# Power_Management.net
KiCad netlist of a schematic drawn in Altium Designer
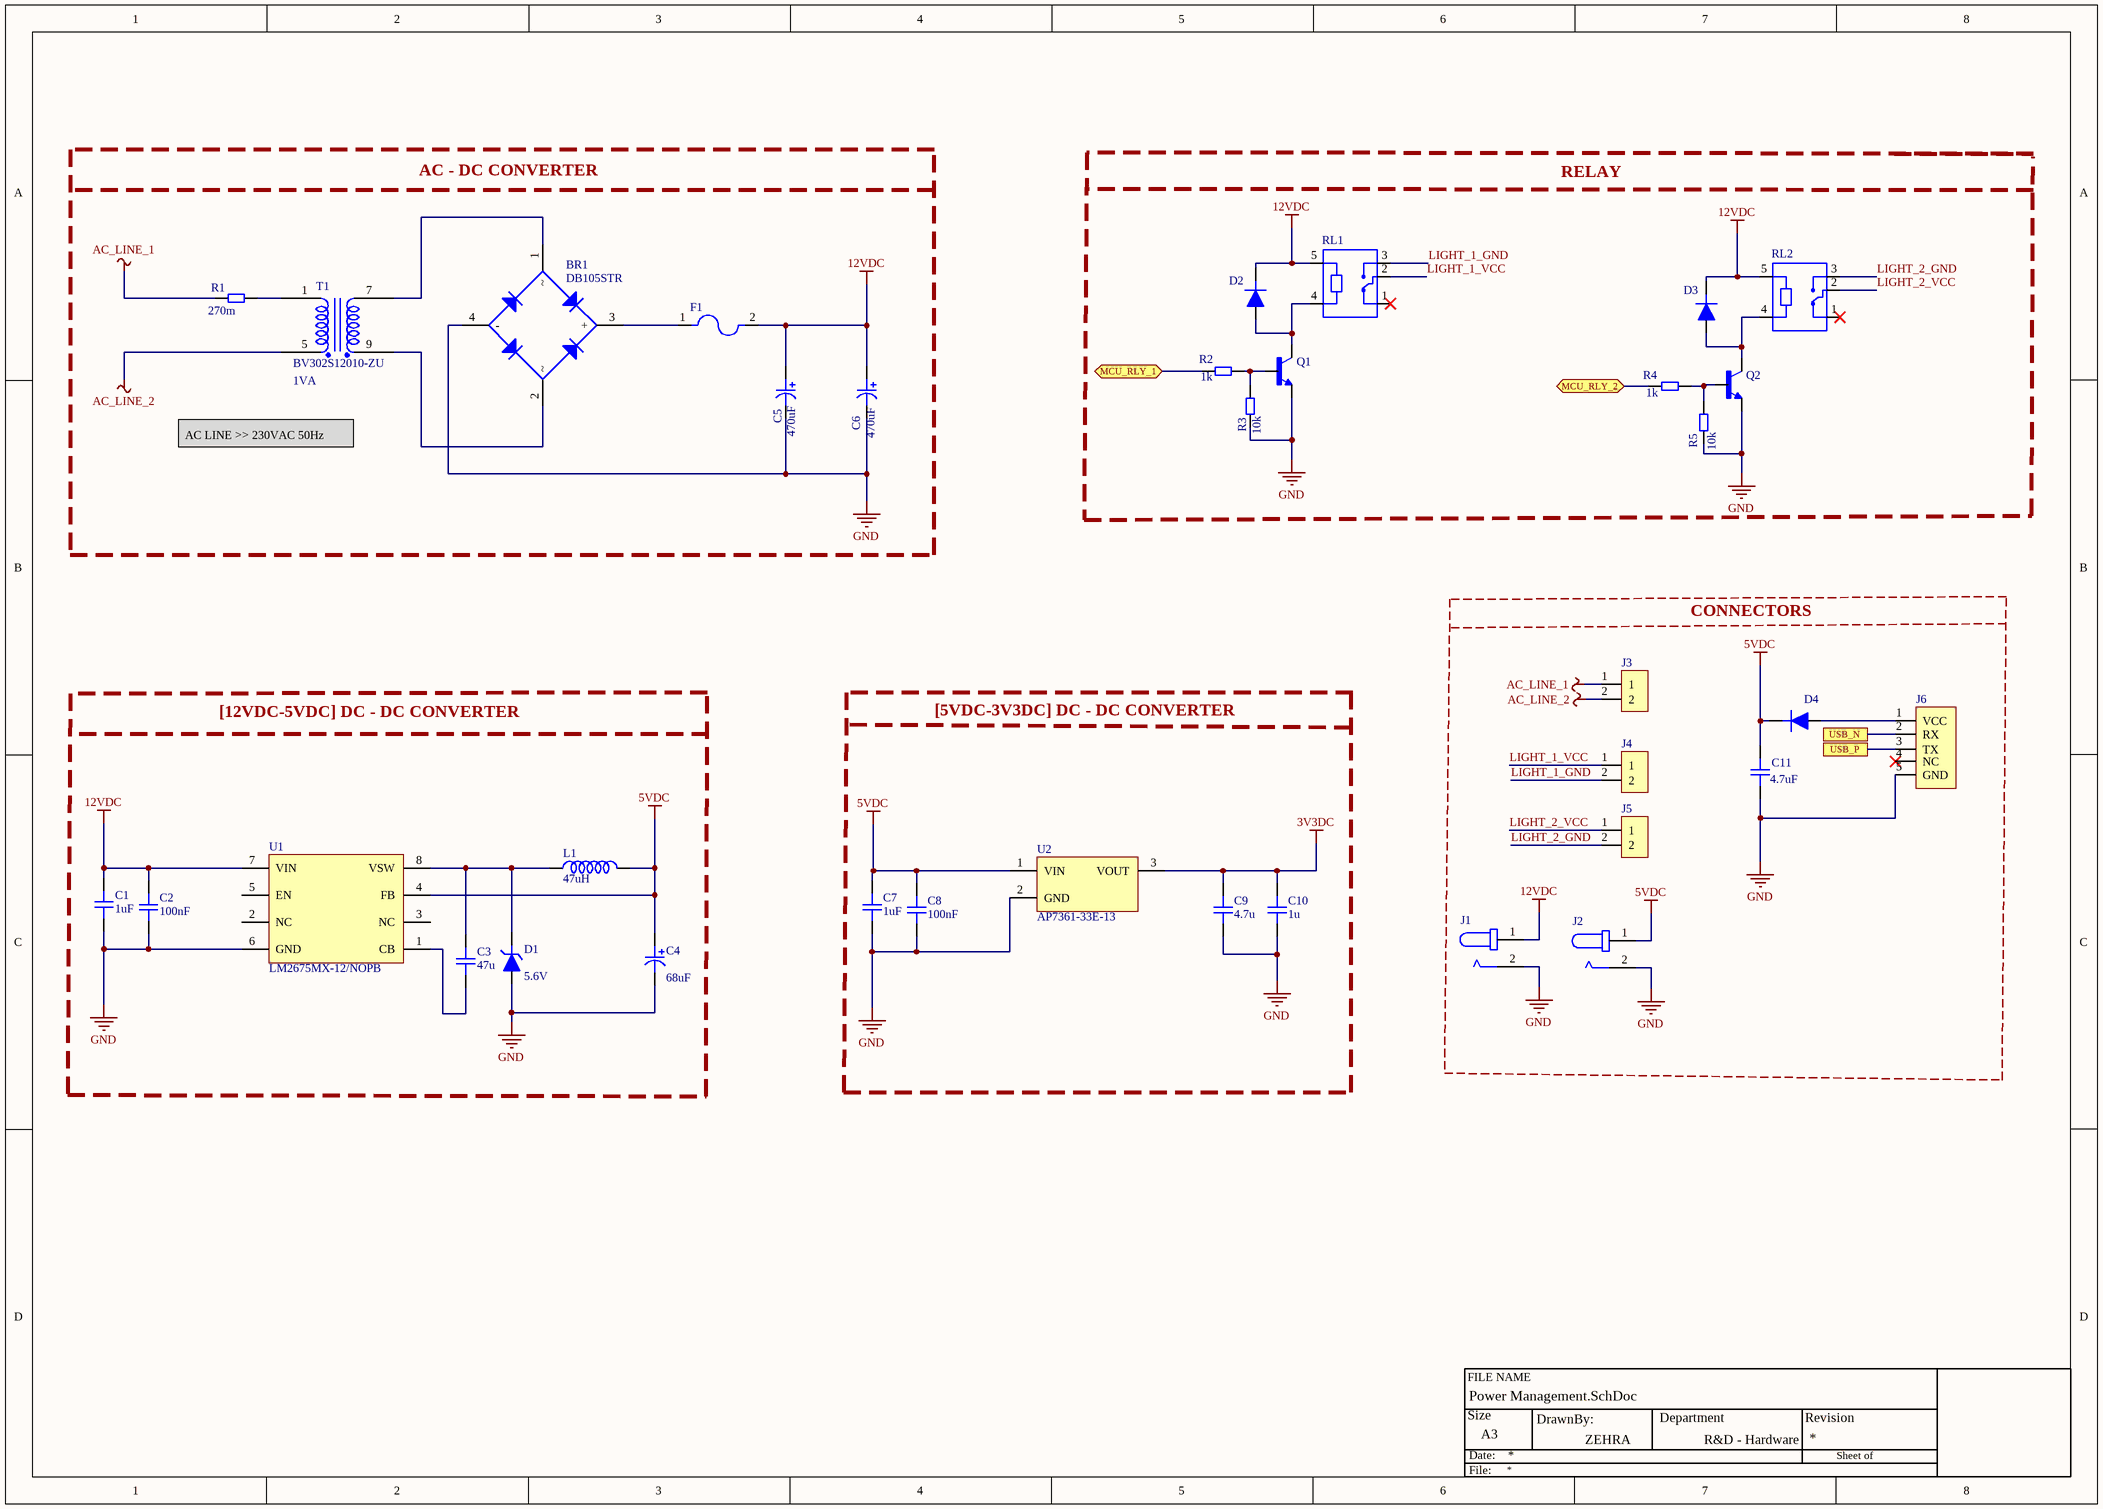
[diagram p0: Power Management.SchDoc]

(export (version "E")
  (design (tool "Eeschema 10.0.6"))
  (components
    (comp (ref "BR1")
      (value "DB105STR")
      (footprint "DB105S")
      (description "Bridge Rect 1PHASE 600V 1A Db-s")
      (fields
        (field (name "MANUFACTURER") "Sangdest Microelectronics")
        (field (name "MANUFACTURER PART NUMBER") "DB105S")
        (field (name "DESIGNER") "ZehraOzkan")
      )
      (libsource (lib "Integrated_Library1") (part "DB105STR"))
    )
    (comp (ref "C1")
      (value "1uF")
      (footprint "CAP_0805")
      (description "Capacitor SMD 0805 10V")
      (fields (field (name "DESIGNER") "ZehraOzkan"))
      (libsource (lib "Integrated_Library1") (part "CAP_0805_10V"))
    )
    (comp (ref "C2")
      (value "100nF")
      (footprint "CAP_0805")
      (description "Capacitor SMD 0805 10V")
      (fields (field (name "DESIGNER") "ZehraOzkan"))
      (libsource (lib "Integrated_Library1") (part "CAP_0805_10V"))
    )
    (comp (ref "C3")
      (value "47u")
      (footprint "CAP_0805")
      (description "Capacitor SMD 0805 10V")
      (fields (field (name "DESIGNER") "ZehraOzkan"))
      (libsource (lib "Integrated_Library1") (part "CAP_0805_10V"))
    )
    (comp (ref "C4")
      (value "EEV686M025A9GAA")
      (footprint "CAP_EEVSERIES")
      (description "Cap Aluminum Lytic 68uF 25V 20% (6.3 X 5.4mm) SMD 240mA 2000h 105C T/R")
      (fields
        (field (name "MANUFACTURER") "KEMET")
        (field (name "TOLERANCE") "20%")
        (field (name "CAPACITANCE") "68uF")
        (field (name "DESIGNER") "ZehraOzkan")
      )
      (libsource (lib "Integrated_Library1") (part "CAP_ALU_68uF"))
    )
    (comp (ref "C5")
      (value "EEV686M025A9GAA")
      (footprint "CAP_EEVSERIES")
      (description "Cap Aluminum Lytic 68uF 25V 20% (6.3 X 5.4mm) SMD 240mA 2000h 105C T/R")
      (fields
        (field (name "MANUFACTURER") "KEMET")
        (field (name "TOLERANCE") "20%")
        (field (name "CAPACITANCE") "470uF")
        (field (name "DESIGNER") "ZehraOzkan")
      )
      (libsource (lib "Integrated_Library1") (part "CAP_ALU_68uF"))
    )
    (comp (ref "C6")
      (value "EEV686M025A9GAA")
      (footprint "CAP_EEVSERIES")
      (description "Cap Aluminum Lytic 68uF 25V 20% (6.3 X 5.4mm) SMD 240mA 2000h 105C T/R")
      (fields
        (field (name "MANUFACTURER") "KEMET")
        (field (name "TOLERANCE") "20%")
        (field (name "CAPACITANCE") "470uF")
        (field (name "DESIGNER") "ZehraOzkan")
      )
      (libsource (lib "Integrated_Library1") (part "CAP_ALU_68uF"))
    )
    (comp (ref "C7")
      (value "1uF")
      (footprint "CAP_0805")
      (description "Capacitor SMD 0805 10V")
      (fields (field (name "DESIGNER") "ZehraOzkan"))
      (libsource (lib "Integrated_Library1") (part "CAP_0805_10V"))
    )
    (comp (ref "C8")
      (value "100nF")
      (footprint "CAP_0805")
      (description "Capacitor SMD 0805 10V")
      (fields (field (name "DESIGNER") "ZehraOzkan"))
      (libsource (lib "Integrated_Library1") (part "CAP_0805_10V"))
    )
    (comp (ref "C9")
      (value "4.7u")
      (footprint "CAP_0805")
      (description "Capacitor SMD 0805 10V")
      (fields (field (name "DESIGNER") "ZehraOzkan"))
      (libsource (lib "Integrated_Library1") (part "CAP_0805_10V"))
    )
    (comp (ref "C10")
      (value "1u")
      (footprint "CAP_0805")
      (description "Capacitor SMD 0805 10V")
      (fields (field (name "DESIGNER") "ZehraOzkan"))
      (libsource (lib "Integrated_Library1") (part "CAP_0805_10V"))
    )
    (comp (ref "C11")
      (value "4.7uF")
      (footprint "CAP_0805")
      (description "Capacitor SMD 0805 10V")
      (fields (field (name "DESIGNER") "ZehraOzkan"))
      (libsource (lib "Integrated_Library1") (part "CAP_0805_10V"))
    )
    (comp (ref "D1")
      (value "1SMB5919BT3G")
      (footprint "1SMB5919BT3G")
      (description "Vz=5.6V 5.32V~5.88V Izt=66.9mA")
      (fields
        (field (name "MANUFACTURER") "ON Semiconductor")
        (field (name "TOLERANCE") "5%")
        (field (name "WORKING VOLTAGE") "5.6V")
        (field (name "DESIGNER") "ZehraOzkan")
      )
      (libsource (lib "Integrated_Library1") (part "1SMB5919BT3G"))
    )
    (comp (ref "D2")
      (value "1N5824")
      (footprint "1N5824")
      (description "Diode Schottky 30V 5A 2-Pin Axial Leaded Tray")
      (fields (field (name "MANUFACTURER") "Microsemi") (field (name "DESIGNER") "ZehraOzkan"))
      (libsource (lib "Integrated_Library1") (part "1N5824"))
    )
    (comp (ref "D3")
      (value "1N5824")
      (footprint "1N5824")
      (description "Diode Schottky 30V 5A 2-Pin Axial Leaded Tray")
      (fields (field (name "MANUFACTURER") "Microsemi") (field (name "DESIGNER") "ZehraOzkan"))
      (libsource (lib "Integrated_Library1") (part "1N5824"))
    )
    (comp (ref "D4")
      (value "1N5824")
      (footprint "1N5824")
      (description "Diode Schottky 30V 5A 2-Pin Axial Leaded Tray")
      (fields (field (name "MANUFACTURER") "Microsemi") (field (name "DESIGNER") "ZehraOzkan"))
      (libsource (lib "Integrated_Library1") (part "1N5824"))
    )
    (comp (ref "F1")
      (value "FUSE 3413.0216.22")
      (footprint "FUSE 3413.0216.22")
      (description "Fuse Chip Fast Acting 1A 32V SMD Solder Pad 1206 Glass T/R VDE/cULus")
      (fields
        (field (name "MANUFACTURER") "Schurter")
        (field (name "MANUFACTURER PART NUMBER") "3413.0216.22")
        (field (name "DESIGNER") "ZehraOzkan")
      )
      (libsource (lib "Integrated_Library1") (part "FUSE 3413.0216.22"))
    )
    (comp (ref "J1")
      (value "PJ-037AH-SMT-TR")
      (footprint "PJ-037AH-SMT-TR")
      (description "2.0 x 6.3 mm, 5.0 A, Horizontal, Surface Mount (SMT), Dc Power Jack Connector")
      (fields (field (name "MANUFACTURER") "CUI") (field (name "DESIGNER") "ZehraOzkan"))
      (libsource (lib "Integrated_Library1") (part "PJ-037AH-SMT-TR"))
    )
    (comp (ref "J2")
      (value "PJ-037AH-SMT-TR")
      (footprint "PJ-037AH-SMT-TR")
      (description "2.0 x 6.3 mm, 5.0 A, Horizontal, Surface Mount (SMT), Dc Power Jack Connector")
      (fields (field (name "MANUFACTURER") "CUI") (field (name "DESIGNER") "ZehraOzkan"))
      (libsource (lib "Integrated_Library1") (part "PJ-037AH-SMT-TR"))
    )
    (comp (ref "J3")
      (value "TBP01R1-508-02BE")
      (footprint "TBP01R1-508-02BE")
      (fields (field (name "DESIGNER") "ZehraOzkan"))
      (libsource (lib "Integrated_Library1") (part "TBP01R1-508-02BE"))
    )
    (comp (ref "J4")
      (value "TBP01R1-508-02BE")
      (footprint "TBP01R1-508-02BE")
      (fields (field (name "DESIGNER") "ZehraOzkan"))
      (libsource (lib "Integrated_Library1") (part "TBP01R1-508-02BE"))
    )
    (comp (ref "J5")
      (value "TBP01R1-508-02BE")
      (footprint "TBP01R1-508-02BE")
      (fields (field (name "DESIGNER") "ZehraOzkan"))
      (libsource (lib "Integrated_Library1") (part "TBP01R1-508-02BE"))
    )
    (comp (ref "J6")
      (value "10118194-0011LF")
      (footprint "10118194-0011LF")
      (fields (field (name "DESIGNER") "ZehraOzkan"))
      (libsource (lib "Integrated_Library1") (part "Micro_B_USB"))
    )
    (comp (ref "L1")
      (value "47uH")
      (footprint "IND_1212")
      (description "Fixed Ind 47UH 390MA 2.3 Ohm SMD")
      (fields
        (field (name "MANUFACTURER") "Wurth Electronics")
        (field (name "MANUFACTURER PART NUMBER") "78438335470")
        (field (name "DESIGNER") "ZehraOzkan")
      )
      (libsource (lib "Integrated_Library1") (part "IND_47uH"))
    )
    (comp (ref "Q1")
      (value "BC237")
      (footprint "BC237")
      (description "Transistor NPN BC237B MOTOROLA milliampere=100 V=45 R204")
      (fields
        (field (name "MANUFACTURER") "ON Semiconductor / Fairchild")
        (field (name "MANUFACTURER PART NUMBER") "BC237B")
        (field (name "DESIGNER") "ZehraOzkan")
      )
      (libsource (lib "Integrated_Library1") (part "BC237"))
    )
    (comp (ref "Q2")
      (value "BC237")
      (footprint "BC237")
      (description "Transistor NPN BC237B MOTOROLA milliampere=100 V=45 R204")
      (fields
        (field (name "MANUFACTURER") "ON Semiconductor / Fairchild")
        (field (name "MANUFACTURER PART NUMBER") "BC237B")
        (field (name "DESIGNER") "ZehraOzkan")
      )
      (libsource (lib "Integrated_Library1") (part "BC237"))
    )
    (comp (ref "R1")
      (value "270m")
      (footprint "RES-0805")
      (description "Res Thick Film 0805 27 Ohm 1% 0.125W(1/8W) ±100ppm/C Pad SMD T/R")
      (fields
        (field (name "MANUFACTURER") "Yageo")
        (field (name "MANUFACTURER PART NUMBER") "RC0805FR-0727RL")
        (field (name "DESIGNER") "ZehraOzkan")
      )
      (libsource (lib "Integrated_Library1") (part "RES-0805-27R"))
    )
    (comp (ref "R2")
      (value "1k")
      (footprint "RES-0805")
      (description "Res Thick Film 0805 27 Ohm 1% 0.125W(1/8W) ±100ppm/C Pad SMD T/R")
      (fields
        (field (name "MANUFACTURER") "Yageo")
        (field (name "MANUFACTURER PART NUMBER") "RC0805FR-0727RL")
        (field (name "DESIGNER") "ZehraOzkan")
      )
      (libsource (lib "Integrated_Library1") (part "RES-0805-27R"))
    )
    (comp (ref "R3")
      (value "10k")
      (footprint "RES-0805")
      (description "Res Thick Film 0805 27 Ohm 1% 0.125W(1/8W) ±100ppm/C Pad SMD T/R")
      (fields
        (field (name "MANUFACTURER") "Yageo")
        (field (name "MANUFACTURER PART NUMBER") "RC0805FR-0727RL")
        (field (name "DESIGNER") "ZehraOzkan")
      )
      (libsource (lib "Integrated_Library1") (part "RES-0805-27R"))
    )
    (comp (ref "R4")
      (value "1k")
      (footprint "RES-0805")
      (description "Res Thick Film 0805 27 Ohm 1% 0.125W(1/8W) ±100ppm/C Pad SMD T/R")
      (fields
        (field (name "MANUFACTURER") "Yageo")
        (field (name "MANUFACTURER PART NUMBER") "RC0805FR-0727RL")
        (field (name "DESIGNER") "ZehraOzkan")
      )
      (libsource (lib "Integrated_Library1") (part "RES-0805-27R"))
    )
    (comp (ref "R5")
      (value "10k")
      (footprint "RES-0805")
      (description "Res Thick Film 0805 27 Ohm 1% 0.125W(1/8W) ±100ppm/C Pad SMD T/R")
      (fields
        (field (name "MANUFACTURER") "Yageo")
        (field (name "MANUFACTURER PART NUMBER") "RC0805FR-0727RL")
        (field (name "DESIGNER") "ZehraOzkan")
      )
      (libsource (lib "Integrated_Library1") (part "RES-0805-27R"))
    )
    (comp (ref "RL1")
      (value "ALQ112")
      (footprint "ALQ112")
      (description "RELAY GEN PURPOSE SPDT 10A 12V")
      (fields (field (name "MANUFACTURER") "Panasonic") (field (name "DESIGNER") "ZehraOzkan"))
      (libsource (lib "Integrated_Library1") (part "ALQ112"))
    )
    (comp (ref "RL2")
      (value "ALQ112")
      (footprint "ALQ112")
      (description "RELAY GEN PURPOSE SPDT 10A 12V")
      (fields (field (name "MANUFACTURER") "Panasonic") (field (name "DESIGNER") "ZehraOzkan"))
      (libsource (lib "Integrated_Library1") (part "ALQ112"))
    )
    (comp (ref "T1")
      (value "BV302S12010-ZU")
      (footprint "BV302S12010")
      (description "PWR XFMR LAMINATED 1VA TH")
      (fields (field (name "RATED POWER") "1VA") (field (name "DESIGNER") "ZehraOzkan"))
      (libsource (lib "Integrated_Library1") (part "BV302S12010-ZU"))
    )
    (comp (ref "U1")
      (value "LM2675MX-12/NOPB")
      (footprint "SOIC-8")
      (description "SIMPLE SWITCHER® 6.5V to 40V, 1A Low Component Count Step-Down Regulator 8-SOIC -40 to 125")
      (fields
        (field (name "MANUFACTURER") "TI National Semiconductor")
        (field (name "DESIGNER") "ZehraOzkan")
      )
      (libsource (lib "Integrated_Library1") (part "LM2675MX-12/NOPB"))
    )
    (comp (ref "U2")
      (value "AP7361-33E-13")
      (footprint "SOT-223")
      (description "AP7361 Series 3.3 V 1 A Low SMT Dropout Fixed-Mode Regulator - SOT-223")
      (fields (field (name "MANUFACTURER") "Diodes") (field (name "DESIGNER") "ZehraOzkan"))
      (libsource (lib "Integrated_Library1") (part "AP7361-33E-13"))
    )
  )
  (nets
    (net (code "1") (name "/LIGHT_1_GND") (class "Default")
      (node (ref "J4") (pin "2") (pinfunction "2_2") (pintype "passive"))
      (node (ref "RL1") (pin "3") (pinfunction "3_3") (pintype "passive"))
    )
    (net (code "2") (name "/LIGHT_1_VCC") (class "Default")
      (node (ref "J4") (pin "1") (pinfunction "1_1") (pintype "passive"))
      (node (ref "RL1") (pin "2") (pinfunction "2_2") (pintype "passive"))
    )
    (net (code "3") (name "/LIGHT_2_GND") (class "Default")
      (node (ref "J5") (pin "2") (pinfunction "2_2") (pintype "passive"))
      (node (ref "RL2") (pin "3") (pinfunction "3_3") (pintype "passive"))
    )
    (net (code "4") (name "/LIGHT_2_VCC") (class "Default")
      (node (ref "J5") (pin "1") (pinfunction "1_1") (pintype "passive"))
      (node (ref "RL2") (pin "2") (pinfunction "2_2") (pintype "passive"))
    )
    (net (code "5") (name "/MCU_RLY_1") (class "Default")
      (node (ref "R2") (pin "2") (pinfunction "2_2") (pintype "passive"))
    )
    (net (code "6") (name "/MCU_RLY_2") (class "Default")
      (node (ref "R4") (pin "2") (pinfunction "2_2") (pintype "passive"))
    )
    (net (code "7") (name "/USB_N") (class "Default")
      (node (ref "J6") (pin "2") (pinfunction "RX_2") (pintype "passive"))
    )
    (net (code "8") (name "/USB_P") (class "Default")
      (node (ref "J6") (pin "3") (pinfunction "TX_3") (pintype "passive"))
    )
    (net (code "9") (name "3V3DC") (class "Default")
      (node (ref "C10") (pin "2") (pinfunction "2_2") (pintype "passive"))
      (node (ref "C9") (pin "2") (pinfunction "2_2") (pintype "passive"))
      (node (ref "U2") (pin "3") (pinfunction "VOUT_3") (pintype "passive"))
    )
    (net (code "10") (name "5VDC") (class "Default")
      (node (ref "C11") (pin "2") (pinfunction "2_2") (pintype "passive"))
      (node (ref "C4") (pin "1") (pinfunction "1_1") (pintype "passive"))
      (node (ref "C7") (pin "2") (pinfunction "2_2") (pintype "passive"))
      (node (ref "C8") (pin "2") (pinfunction "2_2") (pintype "passive"))
      (node (ref "D4") (pin "2") (pinfunction "K_2") (pintype "passive"))
      (node (ref "J2") (pin "1") (pinfunction "1_1") (pintype "passive"))
      (node (ref "L1") (pin "2") (pinfunction "2_2") (pintype "passive"))
      (node (ref "U1") (pin "4") (pinfunction "FB_4") (pintype "power_in"))
      (node (ref "U2") (pin "1") (pinfunction "VIN_1") (pintype "passive"))
    )
    (net (code "11") (name "12VDC") (class "Default")
      (node (ref "C1") (pin "2") (pinfunction "2_2") (pintype "passive"))
      (node (ref "C2") (pin "2") (pinfunction "2_2") (pintype "passive"))
      (node (ref "C5") (pin "1") (pinfunction "1_1") (pintype "passive"))
      (node (ref "C6") (pin "1") (pinfunction "1_1") (pintype "passive"))
      (node (ref "D2") (pin "2") (pinfunction "K_2") (pintype "passive"))
      (node (ref "D3") (pin "2") (pinfunction "K_2") (pintype "passive"))
      (node (ref "F1") (pin "2") (pinfunction "2_2") (pintype "passive"))
      (node (ref "J1") (pin "1") (pinfunction "1_1") (pintype "passive"))
      (node (ref "RL1") (pin "5") (pinfunction "5_5") (pintype "passive"))
      (node (ref "RL2") (pin "5") (pinfunction "5_5") (pintype "passive"))
      (node (ref "U1") (pin "7") (pinfunction "VIN_7") (pintype "passive"))
    )
    (net (code "12") (name "AC_LINE_1") (class "Default")
      (node (ref "J3") (pin "1") (pinfunction "1_1") (pintype "passive"))
      (node (ref "R1") (pin "1") (pinfunction "1_1") (pintype "passive"))
    )
    (net (code "13") (name "AC_LINE_2") (class "Default")
      (node (ref "J3") (pin "2") (pinfunction "2_2") (pintype "passive"))
      (node (ref "T1") (pin "5") (pinfunction "5_5") (pintype "passive"))
    )
    (net (code "14") (name "GND") (class "Default")
      (node (ref "BR1") (pin "4") (pinfunction "-_4") (pintype "passive"))
      (node (ref "C1") (pin "1") (pinfunction "1_1") (pintype "passive"))
      (node (ref "C10") (pin "1") (pinfunction "1_1") (pintype "passive"))
      (node (ref "C11") (pin "1") (pinfunction "1_1") (pintype "passive"))
      (node (ref "C2") (pin "1") (pinfunction "1_1") (pintype "passive"))
      (node (ref "C4") (pin "2") (pinfunction "2_2") (pintype "passive"))
      (node (ref "C5") (pin "2") (pinfunction "2_2") (pintype "passive"))
      (node (ref "C6") (pin "2") (pinfunction "2_2") (pintype "passive"))
      (node (ref "C7") (pin "1") (pinfunction "1_1") (pintype "passive"))
      (node (ref "C8") (pin "1") (pinfunction "1_1") (pintype "passive"))
      (node (ref "C9") (pin "1") (pinfunction "1_1") (pintype "passive"))
      (node (ref "D1") (pin "1") (pinfunction "A_1") (pintype "passive"))
      (node (ref "J1") (pin "2") (pinfunction "2_2") (pintype "passive"))
      (node (ref "J2") (pin "2") (pinfunction "2_2") (pintype "passive"))
      (node (ref "J6") (pin "5") (pinfunction "GND_5") (pintype "passive"))
      (node (ref "Q1") (pin "1") (pinfunction "E_1") (pintype "passive"))
      (node (ref "Q2") (pin "1") (pinfunction "E_1") (pintype "passive"))
      (node (ref "R3") (pin "1") (pinfunction "1_1") (pintype "passive"))
      (node (ref "R5") (pin "1") (pinfunction "1_1") (pintype "passive"))
      (node (ref "U1") (pin "6") (pinfunction "GND_6") (pintype "passive"))
      (node (ref "U2") (pin "2") (pinfunction "GND_2") (pintype "power_in"))
    )
    (net (code "15") (name "Net-(BR1-+)") (class "Default")
      (node (ref "BR1") (pin "3") (pinfunction "+_3") (pintype "passive"))
      (node (ref "F1") (pin "1") (pinfunction "1_1") (pintype "passive"))
    )
    (net (code "16") (name "Net-(BR1-~-Pad1)") (class "Default")
      (node (ref "BR1") (pin "1") (pinfunction "~_1") (pintype "passive"))
      (node (ref "T1") (pin "7") (pinfunction "7_7") (pintype "passive"))
    )
    (net (code "17") (name "Net-(BR1-~-Pad2)") (class "Default")
      (node (ref "BR1") (pin "2") (pinfunction "~_2") (pintype "passive"))
      (node (ref "T1") (pin "9") (pinfunction "9_9") (pintype "passive"))
    )
    (net (code "18") (name "Net-(D1-K)") (class "Default")
      (node (ref "C3") (pin "2") (pinfunction "2_2") (pintype "passive"))
      (node (ref "D1") (pin "2") (pinfunction "K_2") (pintype "passive"))
      (node (ref "L1") (pin "1") (pinfunction "1_1") (pintype "passive"))
      (node (ref "U1") (pin "8") (pinfunction "VSW_8") (pintype "passive"))
    )
    (net (code "19") (name "Net-(D2-A)") (class "Default")
      (node (ref "D2") (pin "1") (pinfunction "A_1") (pintype "passive"))
      (node (ref "Q1") (pin "3") (pinfunction "C_3") (pintype "passive"))
      (node (ref "RL1") (pin "4") (pinfunction "4_4") (pintype "passive"))
    )
    (net (code "20") (name "Net-(D3-A)") (class "Default")
      (node (ref "D3") (pin "1") (pinfunction "A_1") (pintype "passive"))
      (node (ref "Q2") (pin "3") (pinfunction "C_3") (pintype "passive"))
      (node (ref "RL2") (pin "4") (pinfunction "4_4") (pintype "passive"))
    )
    (net (code "21") (name "Net-(D4-A)") (class "Default")
      (node (ref "D4") (pin "1") (pinfunction "A_1") (pintype "passive"))
      (node (ref "J6") (pin "1") (pinfunction "VCC_1") (pintype "passive"))
    )
    (net (code "22") (name "Net-(Q1-B)") (class "Default")
      (node (ref "Q1") (pin "2") (pinfunction "B_2") (pintype "passive"))
      (node (ref "R2") (pin "1") (pinfunction "1_1") (pintype "passive"))
      (node (ref "R3") (pin "2") (pinfunction "2_2") (pintype "passive"))
    )
    (net (code "23") (name "Net-(Q2-B)") (class "Default")
      (node (ref "Q2") (pin "2") (pinfunction "B_2") (pintype "passive"))
      (node (ref "R4") (pin "1") (pinfunction "1_1") (pintype "passive"))
      (node (ref "R5") (pin "2") (pinfunction "2_2") (pintype "passive"))
    )
    (net (code "24") (name "Net-(R1-Pad2)") (class "Default")
      (node (ref "R1") (pin "2") (pinfunction "2_2") (pintype "passive"))
      (node (ref "T1") (pin "1") (pinfunction "1_1") (pintype "passive"))
    )
    (net (code "25") (name "Net-(U1-CB)") (class "Default")
      (node (ref "C3") (pin "1") (pinfunction "1_1") (pintype "passive"))
      (node (ref "U1") (pin "1") (pinfunction "CB_1") (pintype "passive"))
    )
    (net (code "26") (name "unconnected-(J6-NC-Pad4)") (class "Default")
      (node (ref "J6") (pin "4") (pinfunction "NC_4") (pintype "passive+no_connect"))
    )
    (net (code "27") (name "unconnected-(RL1-Pad1)") (class "Default")
      (node (ref "RL1") (pin "1") (pinfunction "1_1") (pintype "passive+no_connect"))
    )
    (net (code "28") (name "unconnected-(RL2-Pad1)") (class "Default")
      (node (ref "RL2") (pin "1") (pinfunction "1_1") (pintype "passive+no_connect"))
    )
    (net (code "29") (name "unconnected-(U1-EN-Pad5)") (class "Default")
      (node (ref "U1") (pin "5") (pinfunction "EN_5") (pintype "passive"))
    )
    (net (code "30") (name "unconnected-(U1-NC-Pad2)") (class "Default")
      (node (ref "U1") (pin "2") (pinfunction "NC_2") (pintype "passive"))
    )
    (net (code "31") (name "unconnected-(U1-NC-Pad3)") (class "Default")
      (node (ref "U1") (pin "3") (pinfunction "NC_3") (pintype "passive"))
    )
  )
)
